# VoltageDivision.net
KiCad netlist of a schematic drawn in Altium Designer
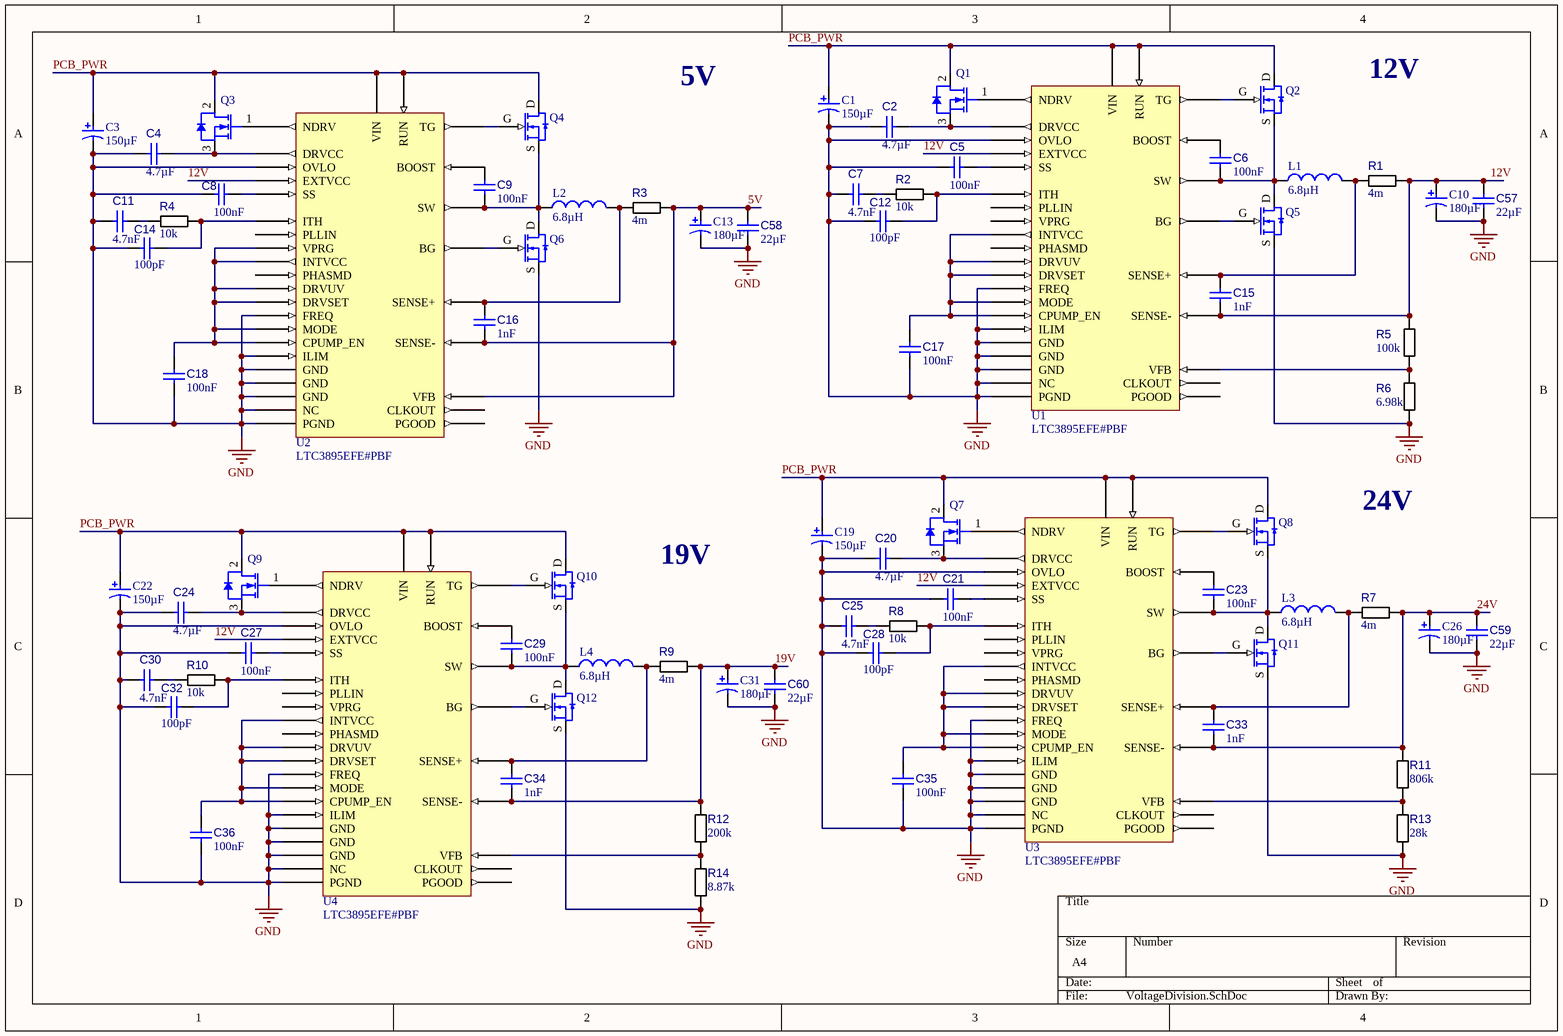
[diagram p0: VoltageDivision.SchDoc]

(export (version "E")
  (design (tool "Eeschema 10.0.6"))
  (components
    (comp (ref "C1")
      (value "150µF")
      (footprint "CAPAE10083X105M")
      (description "Cap Aluminum 150uF 50V 20% Cylindrical 0.34 Ohm 350mA 2000 hr 105°C Emboss T/R")
      (fields (field (name "Comment") "EEE-FN1H151UP"))
      (libsource (lib "Oliver Voorel") (part "CAP-P-2"))
    )
    (comp (ref "C2")
      (value "4.7µF")
      (footprint "FP-GRM31C-0_2-e0_3_0_8-IPC_A")
      (fields (field (name "Comment") "4.7uF 1206"))
      (libsource (lib "Oliver Voorel") (part "CAP-NP-2"))
    )
    (comp (ref "C3")
      (value "150µF")
      (footprint "CAPAE10083X105M")
      (description "Cap Aluminum 150uF 50V 20% Cylindrical 0.34 Ohm 350mA 2000 hr 105°C Emboss T/R")
      (fields (field (name "Comment") "EEE-FN1H151UP"))
      (libsource (lib "Oliver Voorel") (part "CAP-P-2"))
    )
    (comp (ref "C4")
      (value "4.7µF")
      (footprint "FP-GRM31C-0_2-e0_3_0_8-IPC_A")
      (fields (field (name "Comment") "4.7uF 1206"))
      (libsource (lib "Oliver Voorel") (part "CAP-NP-2"))
    )
    (comp (ref "C5")
      (value "100nF")
      (footprint "CAPC1608X10N")
      (fields (field (name "TOLERANCE") "5%") (field (name "Comment") "100nF 0603"))
      (libsource (lib "Oliver Voorel") (part "CAP-NP-2"))
    )
    (comp (ref "C6")
      (value "100nF")
      (footprint "CAPC1608X10N")
      (fields (field (name "TOLERANCE") "5%") (field (name "Comment") "100nF 0603"))
      (libsource (lib "Oliver Voorel") (part "CAP-NP-2"))
    )
    (comp (ref "C7")
      (value "4.7nF")
      (footprint "CAPC1608X10N")
      (fields (field (name "Comment") "CL10B472KB8NNNC"))
      (libsource (lib "Oliver Voorel") (part "CAP-NP-2"))
    )
    (comp (ref "C8")
      (value "100nF")
      (footprint "CAPC1608X10N")
      (fields (field (name "TOLERANCE") "5%") (field (name "Comment") "100nF 0603"))
      (libsource (lib "Oliver Voorel") (part "CAP-NP-2"))
    )
    (comp (ref "C9")
      (value "100nF")
      (footprint "CAPC1608X10N")
      (fields (field (name "TOLERANCE") "5%") (field (name "Comment") "100nF 0603"))
      (libsource (lib "Oliver Voorel") (part "CAP-NP-2"))
    )
    (comp (ref "C10")
      (value "180µF")
      (footprint "CAPAE10083X105M")
      (description "Cap Aluminum 180uF 50V 20% Cylindrical 0.34 Ohm 350mA 2000 hr 105°C Emboss T/R")
      (fields (field (name "TOLERANCE") "20%") (field (name "Comment") "EEEFN1H181UP"))
      (libsource (lib "Oliver Voorel") (part "CAP-P-2"))
    )
    (comp (ref "C11")
      (value "4.7nF")
      (footprint "CAPC1608X10N")
      (fields (field (name "Comment") "CL10B472KB8NNNC"))
      (libsource (lib "Oliver Voorel") (part "CAP-NP-2"))
    )
    (comp (ref "C12")
      (value "100pF")
      (footprint "CAPC1608X10N")
      (description "50V 100pF C0G ±5% 0603 Multilayer Ceramic Capacitors MLCC - SMD/SMT ROHS")
      (fields (field (name "TOLERANCE") "5%") (field (name "Comment") "100pF 0603"))
      (libsource (lib "Oliver Voorel") (part "CAP-NP-2"))
    )
    (comp (ref "C13")
      (value "180µF")
      (footprint "CAPAE10083X105M")
      (description "Cap Aluminum 180uF 50V 20% Cylindrical 0.34 Ohm 350mA 2000 hr 105°C Emboss T/R")
      (fields (field (name "TOLERANCE") "20%") (field (name "Comment") "EEEFN1H181UP"))
      (libsource (lib "Oliver Voorel") (part "CAP-P-2"))
    )
    (comp (ref "C14")
      (value "100pF")
      (footprint "CAPC1608X10N")
      (description "50V 100pF C0G ±5% 0603 Multilayer Ceramic Capacitors MLCC - SMD/SMT ROHS")
      (fields (field (name "TOLERANCE") "5%") (field (name "Comment") "100pF 0603"))
      (libsource (lib "Oliver Voorel") (part "CAP-NP-2"))
    )
    (comp (ref "C15")
      (value "1nF")
      (footprint "CAPC1608X10N")
      (description "50V 1nF X7R ±10% 0603 Multilayer Ceramic Capacitors MLCC - SMD/SMT ROHS")
      (fields (field (name "Comment") "1nF 0603"))
      (libsource (lib "Oliver Voorel") (part "CAP-NP-2"))
    )
    (comp (ref "C16")
      (value "1nF")
      (footprint "CAPC1608X10N")
      (description "50V 1nF X7R ±10% 0603 Multilayer Ceramic Capacitors MLCC - SMD/SMT ROHS")
      (fields (field (name "Comment") "1nF 0603"))
      (libsource (lib "Oliver Voorel") (part "CAP-NP-2"))
    )
    (comp (ref "C17")
      (value "100nF")
      (footprint "CAPC1608X10N")
      (fields (field (name "TOLERANCE") "5%") (field (name "Comment") "100nF 0603"))
      (libsource (lib "Oliver Voorel") (part "CAP-NP-2"))
    )
    (comp (ref "C18")
      (value "100nF")
      (footprint "CAPC1608X10N")
      (fields (field (name "TOLERANCE") "5%") (field (name "Comment") "100nF 0603"))
      (libsource (lib "Oliver Voorel") (part "CAP-NP-2"))
    )
    (comp (ref "C19")
      (value "150µF")
      (footprint "CAPAE10083X105M")
      (description "Cap Aluminum 150uF 50V 20% Cylindrical 0.34 Ohm 350mA 2000 hr 105°C Emboss T/R")
      (fields (field (name "Comment") "EEE-FN1H151UP"))
      (libsource (lib "Oliver Voorel") (part "CAP-P-2"))
    )
    (comp (ref "C20")
      (value "4.7µF")
      (footprint "FP-GRM31C-0_2-e0_3_0_8-IPC_A")
      (fields (field (name "Comment") "4.7uF 1206"))
      (libsource (lib "Oliver Voorel") (part "CAP-NP-2"))
    )
    (comp (ref "C21")
      (value "100nF")
      (footprint "CAPC1608X10N")
      (fields (field (name "TOLERANCE") "5%") (field (name "Comment") "100nF 0603"))
      (libsource (lib "Oliver Voorel") (part "CAP-NP-2"))
    )
    (comp (ref "C22")
      (value "150µF")
      (footprint "CAPAE10083X105M")
      (description "Cap Aluminum 150uF 50V 20% Cylindrical 0.34 Ohm 350mA 2000 hr 105°C Emboss T/R")
      (fields (field (name "Comment") "EEE-FN1H151UP"))
      (libsource (lib "Oliver Voorel") (part "CAP-P-2"))
    )
    (comp (ref "C23")
      (value "100nF")
      (footprint "CAPC1608X10N")
      (fields (field (name "TOLERANCE") "5%") (field (name "Comment") "100nF 0603"))
      (libsource (lib "Oliver Voorel") (part "CAP-NP-2"))
    )
    (comp (ref "C24")
      (value "4.7µF")
      (footprint "FP-GRM31C-0_2-e0_3_0_8-IPC_A")
      (fields (field (name "Comment") "4.7uF 1206"))
      (libsource (lib "Oliver Voorel") (part "CAP-NP-2"))
    )
    (comp (ref "C25")
      (value "4.7nF")
      (footprint "CAPC1608X10N")
      (fields (field (name "Comment") "CL10B472KB8NNNC"))
      (libsource (lib "Oliver Voorel") (part "CAP-NP-2"))
    )
    (comp (ref "C26")
      (value "180µF")
      (footprint "CAPAE10083X105M")
      (description "Cap Aluminum 180uF 50V 20% Cylindrical 0.34 Ohm 350mA 2000 hr 105°C Emboss T/R")
      (fields (field (name "TOLERANCE") "20%") (field (name "Comment") "EEEFN1H181UP"))
      (libsource (lib "Oliver Voorel") (part "CAP-P-2"))
    )
    (comp (ref "C27")
      (value "100nF")
      (footprint "CAPC1608X10N")
      (fields (field (name "TOLERANCE") "5%") (field (name "Comment") "100nF 0603"))
      (libsource (lib "Oliver Voorel") (part "CAP-NP-2"))
    )
    (comp (ref "C28")
      (value "100pF")
      (footprint "CAPC1608X10N")
      (description "50V 100pF C0G ±5% 0603 Multilayer Ceramic Capacitors MLCC - SMD/SMT ROHS")
      (fields (field (name "TOLERANCE") "5%") (field (name "Comment") "100pF 0603"))
      (libsource (lib "Oliver Voorel") (part "CAP-NP-2"))
    )
    (comp (ref "C29")
      (value "100nF")
      (footprint "CAPC1608X10N")
      (fields (field (name "TOLERANCE") "5%") (field (name "Comment") "100nF 0603"))
      (libsource (lib "Oliver Voorel") (part "CAP-NP-2"))
    )
    (comp (ref "C30")
      (value "4.7nF")
      (footprint "CAPC1608X10N")
      (fields (field (name "Comment") "CL10B472KB8NNNC"))
      (libsource (lib "Oliver Voorel") (part "CAP-NP-2"))
    )
    (comp (ref "C31")
      (value "180µF")
      (footprint "CAPAE10083X105M")
      (description "Cap Aluminum 180uF 50V 20% Cylindrical 0.34 Ohm 350mA 2000 hr 105°C Emboss T/R")
      (fields (field (name "TOLERANCE") "20%") (field (name "Comment") "EEEFN1H181UP"))
      (libsource (lib "Oliver Voorel") (part "CAP-P-2"))
    )
    (comp (ref "C32")
      (value "100pF")
      (footprint "CAPC1608X10N")
      (description "50V 100pF C0G ±5% 0603 Multilayer Ceramic Capacitors MLCC - SMD/SMT ROHS")
      (fields (field (name "TOLERANCE") "5%") (field (name "Comment") "100pF 0603"))
      (libsource (lib "Oliver Voorel") (part "CAP-NP-2"))
    )
    (comp (ref "C33")
      (value "1nF")
      (footprint "CAPC1608X10N")
      (description "50V 1nF X7R ±10% 0603 Multilayer Ceramic Capacitors MLCC - SMD/SMT ROHS")
      (fields (field (name "Comment") "1nF 0603"))
      (libsource (lib "Oliver Voorel") (part "CAP-NP-2"))
    )
    (comp (ref "C34")
      (value "1nF")
      (footprint "CAPC1608X10N")
      (description "50V 1nF X7R ±10% 0603 Multilayer Ceramic Capacitors MLCC - SMD/SMT ROHS")
      (fields (field (name "Comment") "1nF 0603"))
      (libsource (lib "Oliver Voorel") (part "CAP-NP-2"))
    )
    (comp (ref "C35")
      (value "100nF")
      (footprint "CAPC1608X10N")
      (fields (field (name "TOLERANCE") "5%") (field (name "Comment") "100nF 0603"))
      (libsource (lib "Oliver Voorel") (part "CAP-NP-2"))
    )
    (comp (ref "C36")
      (value "100nF")
      (footprint "CAPC1608X10N")
      (fields (field (name "TOLERANCE") "5%") (field (name "Comment") "100nF 0603"))
      (libsource (lib "Oliver Voorel") (part "CAP-NP-2"))
    )
    (comp (ref "C57")
      (value "22µF")
      (footprint "CAPC5750X31N")
      (description "50V 22uF X7R ±10% 2220  Multilayer Ceramic Capacitors MLCC - SMD/SMT ROHS")
      (fields (field (name "TOLERANCE") "10%") (field (name "Comment") "FS55X226K500EHG"))
      (libsource (lib "Oliver Voorel") (part "CAP-NP-2"))
    )
    (comp (ref "C58")
      (value "22µF")
      (footprint "CAPC5750X31N")
      (description "50V 22uF X7R ±10% 2220  Multilayer Ceramic Capacitors MLCC - SMD/SMT ROHS")
      (fields (field (name "TOLERANCE") "10%") (field (name "Comment") "FS55X226K500EHG"))
      (libsource (lib "Oliver Voorel") (part "CAP-NP-2"))
    )
    (comp (ref "C59")
      (value "22µF")
      (footprint "CAPC5750X31N")
      (description "50V 22uF X7R ±10% 2220  Multilayer Ceramic Capacitors MLCC - SMD/SMT ROHS")
      (fields (field (name "TOLERANCE") "10%") (field (name "Comment") "FS55X226K500EHG"))
      (libsource (lib "Oliver Voorel") (part "CAP-NP-2"))
    )
    (comp (ref "C60")
      (value "22µF")
      (footprint "CAPC5750X31N")
      (description "50V 22uF X7R ±10% 2220  Multilayer Ceramic Capacitors MLCC - SMD/SMT ROHS")
      (fields (field (name "TOLERANCE") "10%") (field (name "Comment") "FS55X226K500EHG"))
      (libsource (lib "Oliver Voorel") (part "CAP-NP-2"))
    )
    (comp (ref "L1")
      (value "6.8µH")
      (footprint "INDP134126X50N")
      (description "12A 6.8uH ±20% 16A SMD,13.5x12.6mm  Power Inductors ROHS")
      (fields (field (name "TOLERANCE") "20%") (field (name "Comment") "6.8uH"))
      (libsource (lib "Oliver Voorel") (part "IND-2"))
    )
    (comp (ref "L2")
      (value "6.8µH")
      (footprint "INDP134126X50N")
      (description "12A 6.8uH ±20% 16A SMD,13.5x12.6mm  Power Inductors ROHS")
      (fields (field (name "TOLERANCE") "20%") (field (name "Comment") "6.8uH"))
      (libsource (lib "Oliver Voorel") (part "IND-2"))
    )
    (comp (ref "L3")
      (value "6.8µH")
      (footprint "INDP134126X50N")
      (description "12A 6.8uH ±20% 16A SMD,13.5x12.6mm  Power Inductors ROHS")
      (fields (field (name "TOLERANCE") "20%") (field (name "Comment") "6.8uH"))
      (libsource (lib "Oliver Voorel") (part "IND-2"))
    )
    (comp (ref "L4")
      (value "6.8µH")
      (footprint "INDP134126X50N")
      (description "12A 6.8uH ±20% 16A SMD,13.5x12.6mm  Power Inductors ROHS")
      (fields (field (name "TOLERANCE") "20%") (field (name "Comment") "6.8uH"))
      (libsource (lib "Oliver Voorel") (part "IND-2"))
    )
    (comp (ref "Q1")
      (value "IPD320N20N3GATMA1")
      (footprint "INF-PG-TO252-3-11_A_L")
      (libsource (lib "Oliver Voorel") (part "INF-NEMOS-GDS-3"))
    )
    (comp (ref "Q2")
      (value "BSC028N06LS3GATMA1")
      (footprint "INF-PG-TDSON-8-1_V")
      (libsource (lib "Oliver Voorel") (part "N-channel MOSFET"))
    )
    (comp (ref "Q3")
      (value "IPD320N20N3GATMA1")
      (footprint "INF-PG-TO252-3-11_A_L")
      (libsource (lib "Oliver Voorel") (part "INF-NEMOS-GDS-3"))
    )
    (comp (ref "Q4")
      (value "BSC028N06LS3GATMA1")
      (footprint "INF-PG-TDSON-8-1_V")
      (libsource (lib "Oliver Voorel") (part "N-channel MOSFET"))
    )
    (comp (ref "Q5")
      (value "BSC028N06LS3GATMA1")
      (footprint "INF-PG-TDSON-8-1_V")
      (libsource (lib "Oliver Voorel") (part "N-channel MOSFET"))
    )
    (comp (ref "Q6")
      (value "BSC028N06LS3GATMA1")
      (footprint "INF-PG-TDSON-8-1_V")
      (libsource (lib "Oliver Voorel") (part "N-channel MOSFET"))
    )
    (comp (ref "Q7")
      (value "IPD320N20N3GATMA1")
      (footprint "INF-PG-TO252-3-11_A_L")
      (libsource (lib "Oliver Voorel") (part "INF-NEMOS-GDS-3"))
    )
    (comp (ref "Q8")
      (value "BSC028N06LS3GATMA1")
      (footprint "INF-PG-TDSON-8-1_V")
      (libsource (lib "Oliver Voorel") (part "N-channel MOSFET"))
    )
    (comp (ref "Q9")
      (value "IPD320N20N3GATMA1")
      (footprint "INF-PG-TO252-3-11_A_L")
      (libsource (lib "Oliver Voorel") (part "INF-NEMOS-GDS-3"))
    )
    (comp (ref "Q10")
      (value "BSC028N06LS3GATMA1")
      (footprint "INF-PG-TDSON-8-1_V")
      (libsource (lib "Oliver Voorel") (part "N-channel MOSFET"))
    )
    (comp (ref "Q11")
      (value "BSC028N06LS3GATMA1")
      (footprint "INF-PG-TDSON-8-1_V")
      (libsource (lib "Oliver Voorel") (part "N-channel MOSFET"))
    )
    (comp (ref "Q12")
      (value "BSC028N06LS3GATMA1")
      (footprint "INF-PG-TDSON-8-1_V")
      (libsource (lib "Oliver Voorel") (part "N-channel MOSFET"))
    )
    (comp (ref "R1")
      (value "4m")
      (footprint "RESC6432X09N")
      (description "2W 4mΩ ±50ppm/℃ ±1% 2512  Current Sense Resistors/Shunt Resistors ROHS")
      (fields (field (name "TOLERANCE") "1%") (field (name "POWER") "2W"))
      (libsource (lib "Oliver Voorel") (part "RES-2"))
    )
    (comp (ref "R2")
      (value "10k")
      (footprint "RESC1608X06N")
      (fields
        (field (name "POWER") "100mW")
        (field (name "TOLERANCE") "1%")
        (field (name "Comment") "10k 0603")
      )
      (libsource (lib "Oliver Voorel") (part "RES-2"))
    )
    (comp (ref "R3")
      (value "4m")
      (footprint "RESC6432X09N")
      (description "2W 4mΩ ±50ppm/℃ ±1% 2512  Current Sense Resistors/Shunt Resistors ROHS")
      (fields (field (name "TOLERANCE") "1%") (field (name "POWER") "2W"))
      (libsource (lib "Oliver Voorel") (part "RES-2"))
    )
    (comp (ref "R4")
      (value "10k")
      (footprint "RESC1608X06N")
      (fields
        (field (name "POWER") "100mW")
        (field (name "TOLERANCE") "1%")
        (field (name "Comment") "10k 0603")
      )
      (libsource (lib "Oliver Voorel") (part "RES-2"))
    )
    (comp (ref "R5")
      (value "100k")
      (footprint "RESC1608X06N")
      (description "100mW Thick Film Resistors 75V ±100ppm/℃ ±1% 100kΩ 0603 Chip Resistor - Surface Mount ROHS")
      (fields (field (name "POWER") "100mW") (field (name "TOLERANCE") "1%"))
      (libsource (lib "Oliver Voorel") (part "RES-2"))
    )
    (comp (ref "R6")
      (value "6.98k")
      (footprint "RESC1608X06N")
      (description "100mW Thick Film Resistors 75V ±100ppm/℃ ±1% 6.98kΩ 0603 Chip Resistor - Surface Mount ROHS")
      (fields (field (name "POWER") "100mW") (field (name "TOLERANCE") "1%"))
      (libsource (lib "Oliver Voorel") (part "RES-2"))
    )
    (comp (ref "R7")
      (value "4m")
      (footprint "RESC6432X09N")
      (description "2W 4mΩ ±50ppm/℃ ±1% 2512  Current Sense Resistors/Shunt Resistors ROHS")
      (fields (field (name "TOLERANCE") "1%") (field (name "POWER") "2W"))
      (libsource (lib "Oliver Voorel") (part "RES-2"))
    )
    (comp (ref "R8")
      (value "10k")
      (footprint "RESC1608X06N")
      (fields
        (field (name "POWER") "100mW")
        (field (name "TOLERANCE") "1%")
        (field (name "Comment") "10k 0603")
      )
      (libsource (lib "Oliver Voorel") (part "RES-2"))
    )
    (comp (ref "R9")
      (value "4m")
      (footprint "RESC6432X09N")
      (description "2W 4mΩ ±50ppm/℃ ±1% 2512  Current Sense Resistors/Shunt Resistors ROHS")
      (fields (field (name "TOLERANCE") "1%") (field (name "POWER") "2W"))
      (libsource (lib "Oliver Voorel") (part "RES-2"))
    )
    (comp (ref "R10")
      (value "10k")
      (footprint "RESC1608X06N")
      (fields
        (field (name "POWER") "100mW")
        (field (name "TOLERANCE") "1%")
        (field (name "Comment") "10k 0603")
      )
      (libsource (lib "Oliver Voorel") (part "RES-2"))
    )
    (comp (ref "R11")
      (value "806k")
      (footprint "RESC1608X06N")
      (fields
        (field (name "TOLERANCE") "1%")
        (field (name "POWER") "100mW")
        (field (name "Comment") "806k 0603")
      )
      (libsource (lib "Oliver Voorel") (part "RES-2"))
    )
    (comp (ref "R12")
      (value "200k")
      (footprint "RESC1608X06N")
      (fields
        (field (name "TOLERANCE") "1%")
        (field (name "POWER") "100mW")
        (field (name "Comment") "200kR 0603")
      )
      (libsource (lib "Oliver Voorel") (part "RES-2"))
    )
    (comp (ref "R13")
      (value "28k")
      (footprint "RESC1608X06N")
      (fields
        (field (name "TOLERANCE") "1%")
        (field (name "POWER") "100mW")
        (field (name "Comment") "28k 0603")
      )
      (libsource (lib "Oliver Voorel") (part "RES-2"))
    )
    (comp (ref "R14")
      (value "8.87k")
      (footprint "RESC1608X06N")
      (fields
        (field (name "TOLERANCE") "1%")
        (field (name "POWER") "100mW")
        (field (name "Comment") "8.87k 0603")
      )
      (libsource (lib "Oliver Voorel") (part "RES-2"))
    )
    (comp (ref "U1")
      (value "LTC3895EFE#PBF")
      (footprint "TSSOP50P640X120_HS-39N")
      (description "Switching Controller, Current-mode, 900kHz Switching Freq-Max, CMOS, PDSO38")
      (libsource (lib "Oliver Voorel") (part "LTC3895HFE#PBF-Symbol-1"))
    )
    (comp (ref "U2")
      (value "LTC3895EFE#PBF")
      (footprint "TSSOP50P640X120_HS-39N")
      (description "Switching Controller, Current-mode, 900kHz Switching Freq-Max, CMOS, PDSO38")
      (libsource (lib "Oliver Voorel") (part "LTC3895HFE#PBF-Symbol-1"))
    )
    (comp (ref "U3")
      (value "LTC3895EFE#PBF")
      (footprint "TSSOP50P640X120_HS-39N")
      (description "Switching Controller, Current-mode, 900kHz Switching Freq-Max, CMOS, PDSO38")
      (libsource (lib "Oliver Voorel") (part "LTC3895HFE#PBF-Symbol-1"))
    )
    (comp (ref "U4")
      (value "LTC3895EFE#PBF")
      (footprint "TSSOP50P640X120_HS-39N")
      (description "Switching Controller, Current-mode, 900kHz Switching Freq-Max, CMOS, PDSO38")
      (libsource (lib "Oliver Voorel") (part "LTC3895HFE#PBF-Symbol-1"))
    )
  )
  (nets
    (net (code "1") (name "/5V") (class "Default")
      (node (ref "C13") (pin "1") (pinfunction "1_1") (pintype "passive"))
      (node (ref "C16") (pin "1") (pinfunction "1_1") (pintype "passive"))
      (node (ref "C58") (pin "1") (pinfunction "1_1") (pintype "passive"))
      (node (ref "R3") (pin "2") (pinfunction "2_2") (pintype "passive"))
      (node (ref "U2") (pin "4") (pinfunction "SENSE-_4") (pintype "input"))
      (node (ref "U2") (pin "6") (pinfunction "VFB_6") (pintype "input"))
    )
    (net (code "2") (name "/12V") (class "Default")
      (node (ref "C10") (pin "1") (pinfunction "1_1") (pintype "passive"))
      (node (ref "C15") (pin "1") (pinfunction "1_1") (pintype "passive"))
      (node (ref "C57") (pin "1") (pinfunction "1_1") (pintype "passive"))
      (node (ref "R1") (pin "2") (pinfunction "2_2") (pintype "passive"))
      (node (ref "R5") (pin "2") (pinfunction "2_2") (pintype "passive"))
      (node (ref "U1") (pin "32") (pinfunction "EXTVCC_32") (pintype "input"))
      (node (ref "U1") (pin "4") (pinfunction "SENSE-_4") (pintype "input"))
      (node (ref "U2") (pin "32") (pinfunction "EXTVCC_32") (pintype "input"))
      (node (ref "U3") (pin "32") (pinfunction "EXTVCC_32") (pintype "input"))
      (node (ref "U4") (pin "32") (pinfunction "EXTVCC_32") (pintype "input"))
    )
    (net (code "3") (name "/19V") (class "Default")
      (node (ref "C31") (pin "1") (pinfunction "1_1") (pintype "passive"))
      (node (ref "C34") (pin "1") (pinfunction "1_1") (pintype "passive"))
      (node (ref "C60") (pin "1") (pinfunction "1_1") (pintype "passive"))
      (node (ref "R12") (pin "1") (pinfunction "1_1") (pintype "passive"))
      (node (ref "R9") (pin "2") (pinfunction "2_2") (pintype "passive"))
      (node (ref "U4") (pin "4") (pinfunction "SENSE-_4") (pintype "input"))
    )
    (net (code "4") (name "/24V") (class "Default")
      (node (ref "C26") (pin "1") (pinfunction "1_1") (pintype "passive"))
      (node (ref "C33") (pin "1") (pinfunction "1_1") (pintype "passive"))
      (node (ref "C59") (pin "1") (pinfunction "1_1") (pintype "passive"))
      (node (ref "R11") (pin "2") (pinfunction "2_2") (pintype "passive"))
      (node (ref "R7") (pin "2") (pinfunction "2_2") (pintype "passive"))
      (node (ref "U3") (pin "4") (pinfunction "SENSE-_4") (pintype "input"))
    )
    (net (code "5") (name "/PCB_PWR") (class "Default")
      (node (ref "C1") (pin "1") (pinfunction "1_1") (pintype "passive"))
      (node (ref "C19") (pin "1") (pinfunction "1_1") (pintype "passive"))
      (node (ref "C22") (pin "1") (pinfunction "1_1") (pintype "passive"))
      (node (ref "C3") (pin "1") (pinfunction "1_1") (pintype "passive"))
      (node (ref "Q1") (pin "2") (pinfunction "DRAIN_2") (pintype "passive"))
      (node (ref "Q10") (pin "D") (pinfunction "D_D") (pintype "passive"))
      (node (ref "Q2") (pin "D") (pinfunction "D_D") (pintype "passive"))
      (node (ref "Q3") (pin "2") (pinfunction "DRAIN_2") (pintype "passive"))
      (node (ref "Q4") (pin "D") (pinfunction "D_D") (pintype "passive"))
      (node (ref "Q7") (pin "2") (pinfunction "DRAIN_2") (pintype "passive"))
      (node (ref "Q8") (pin "D") (pinfunction "D_D") (pintype "passive"))
      (node (ref "Q9") (pin "2") (pinfunction "DRAIN_2") (pintype "passive"))
      (node (ref "U1") (pin "30") (pinfunction "VIN_30") (pintype "power_in"))
      (node (ref "U1") (pin "34") (pinfunction "RUN_34") (pintype "input"))
      (node (ref "U2") (pin "30") (pinfunction "VIN_30") (pintype "power_in"))
      (node (ref "U2") (pin "34") (pinfunction "RUN_34") (pintype "input"))
      (node (ref "U3") (pin "30") (pinfunction "VIN_30") (pintype "power_in"))
      (node (ref "U3") (pin "34") (pinfunction "RUN_34") (pintype "input"))
      (node (ref "U4") (pin "30") (pinfunction "VIN_30") (pintype "power_in"))
      (node (ref "U4") (pin "34") (pinfunction "RUN_34") (pintype "input"))
    )
    (net (code "6") (name "GND") (class "Default")
      (node (ref "C1") (pin "2") (pinfunction "2_2") (pintype "passive"))
      (node (ref "C10") (pin "2") (pinfunction "2_2") (pintype "passive"))
      (node (ref "C11") (pin "1") (pinfunction "1_1") (pintype "passive"))
      (node (ref "C12") (pin "1") (pinfunction "1_1") (pintype "passive"))
      (node (ref "C13") (pin "2") (pinfunction "2_2") (pintype "passive"))
      (node (ref "C14") (pin "1") (pinfunction "1_1") (pintype "passive"))
      (node (ref "C17") (pin "1") (pinfunction "1_1") (pintype "passive"))
      (node (ref "C18") (pin "1") (pinfunction "1_1") (pintype "passive"))
      (node (ref "C19") (pin "2") (pinfunction "2_2") (pintype "passive"))
      (node (ref "C2") (pin "1") (pinfunction "1_1") (pintype "passive"))
      (node (ref "C20") (pin "1") (pinfunction "1_1") (pintype "passive"))
      (node (ref "C21") (pin "2") (pinfunction "2_2") (pintype "passive"))
      (node (ref "C22") (pin "2") (pinfunction "2_2") (pintype "passive"))
      (node (ref "C24") (pin "1") (pinfunction "1_1") (pintype "passive"))
      (node (ref "C25") (pin "1") (pinfunction "1_1") (pintype "passive"))
      (node (ref "C26") (pin "2") (pinfunction "2_2") (pintype "passive"))
      (node (ref "C27") (pin "2") (pinfunction "2_2") (pintype "passive"))
      (node (ref "C28") (pin "1") (pinfunction "1_1") (pintype "passive"))
      (node (ref "C3") (pin "2") (pinfunction "2_2") (pintype "passive"))
      (node (ref "C30") (pin "1") (pinfunction "1_1") (pintype "passive"))
      (node (ref "C31") (pin "2") (pinfunction "2_2") (pintype "passive"))
      (node (ref "C32") (pin "1") (pinfunction "1_1") (pintype "passive"))
      (node (ref "C35") (pin "1") (pinfunction "1_1") (pintype "passive"))
      (node (ref "C36") (pin "1") (pinfunction "1_1") (pintype "passive"))
      (node (ref "C4") (pin "1") (pinfunction "1_1") (pintype "passive"))
      (node (ref "C5") (pin "2") (pinfunction "2_2") (pintype "passive"))
      (node (ref "C57") (pin "2") (pinfunction "2_2") (pintype "passive"))
      (node (ref "C58") (pin "2") (pinfunction "2_2") (pintype "passive"))
      (node (ref "C59") (pin "2") (pinfunction "2_2") (pintype "passive"))
      (node (ref "C60") (pin "2") (pinfunction "2_2") (pintype "passive"))
      (node (ref "C7") (pin "1") (pinfunction "1_1") (pintype "passive"))
      (node (ref "C8") (pin "2") (pinfunction "2_2") (pintype "passive"))
      (node (ref "Q11") (pin "S") (pinfunction "S_S") (pintype "passive"))
      (node (ref "Q12") (pin "S") (pinfunction "S_S") (pintype "passive"))
      (node (ref "Q5") (pin "S") (pinfunction "S_S") (pintype "passive"))
      (node (ref "Q6") (pin "S") (pinfunction "S_S") (pintype "passive"))
      (node (ref "R13") (pin "1") (pinfunction "1_1") (pintype "passive"))
      (node (ref "R14") (pin "1") (pinfunction "1_1") (pintype "passive"))
      (node (ref "R6") (pin "1") (pinfunction "1_1") (pintype "passive"))
      (node (ref "U1") (pin "1") (pinfunction "OVLO_1") (pintype "input"))
      (node (ref "U1") (pin "12") (pinfunction "GND_12") (pintype "power_in"))
      (node (ref "U1") (pin "15") (pinfunction "GND_15") (pintype "power_in"))
      (node (ref "U1") (pin "16") (pinfunction "NC_16") (pintype "passive"))
      (node (ref "U1") (pin "17") (pinfunction "FREQ_17") (pintype "input"))
      (node (ref "U1") (pin "37") (pinfunction "ILIM_37") (pintype "input"))
      (node (ref "U1") (pin "39") (pinfunction "PGND_39") (pintype "power_in"))
      (node (ref "U1") (pin "9") (pinfunction "GND_9") (pintype "power_in"))
      (node (ref "U2") (pin "1") (pinfunction "OVLO_1") (pintype "input"))
      (node (ref "U2") (pin "12") (pinfunction "GND_12") (pintype "power_in"))
      (node (ref "U2") (pin "15") (pinfunction "GND_15") (pintype "power_in"))
      (node (ref "U2") (pin "16") (pinfunction "NC_16") (pintype "passive"))
      (node (ref "U2") (pin "17") (pinfunction "FREQ_17") (pintype "input"))
      (node (ref "U2") (pin "37") (pinfunction "ILIM_37") (pintype "input"))
      (node (ref "U2") (pin "39") (pinfunction "PGND_39") (pintype "power_in"))
      (node (ref "U2") (pin "9") (pinfunction "GND_9") (pintype "power_in"))
      (node (ref "U3") (pin "1") (pinfunction "OVLO_1") (pintype "input"))
      (node (ref "U3") (pin "12") (pinfunction "GND_12") (pintype "power_in"))
      (node (ref "U3") (pin "15") (pinfunction "GND_15") (pintype "power_in"))
      (node (ref "U3") (pin "16") (pinfunction "NC_16") (pintype "passive"))
      (node (ref "U3") (pin "17") (pinfunction "FREQ_17") (pintype "input"))
      (node (ref "U3") (pin "37") (pinfunction "ILIM_37") (pintype "input"))
      (node (ref "U3") (pin "39") (pinfunction "PGND_39") (pintype "power_in"))
      (node (ref "U3") (pin "9") (pinfunction "GND_9") (pintype "power_in"))
      (node (ref "U4") (pin "1") (pinfunction "OVLO_1") (pintype "input"))
      (node (ref "U4") (pin "12") (pinfunction "GND_12") (pintype "power_in"))
      (node (ref "U4") (pin "15") (pinfunction "GND_15") (pintype "power_in"))
      (node (ref "U4") (pin "16") (pinfunction "NC_16") (pintype "passive"))
      (node (ref "U4") (pin "17") (pinfunction "FREQ_17") (pintype "input"))
      (node (ref "U4") (pin "37") (pinfunction "ILIM_37") (pintype "input"))
      (node (ref "U4") (pin "39") (pinfunction "PGND_39") (pintype "power_in"))
      (node (ref "U4") (pin "9") (pinfunction "GND_9") (pintype "power_in"))
    )
    (net (code "7") (name "Net-(C7-Pad2)") (class "Default")
      (node (ref "C7") (pin "2") (pinfunction "2_2") (pintype "passive"))
      (node (ref "R2") (pin "1") (pinfunction "1_1") (pintype "passive"))
    )
    (net (code "8") (name "Net-(C11-Pad2)") (class "Default")
      (node (ref "C11") (pin "2") (pinfunction "2_2") (pintype "passive"))
      (node (ref "R4") (pin "1") (pinfunction "1_1") (pintype "passive"))
    )
    (net (code "9") (name "Net-(C25-Pad2)") (class "Default")
      (node (ref "C25") (pin "2") (pinfunction "2_2") (pintype "passive"))
      (node (ref "R8") (pin "1") (pinfunction "1_1") (pintype "passive"))
    )
    (net (code "10") (name "Net-(C30-Pad2)") (class "Default")
      (node (ref "C30") (pin "2") (pinfunction "2_2") (pintype "passive"))
      (node (ref "R10") (pin "1") (pinfunction "1_1") (pintype "passive"))
    )
    (net (code "11") (name "Net-(Q1-GATE)") (class "Default")
      (node (ref "Q1") (pin "1") (pinfunction "GATE_1") (pintype "passive"))
      (node (ref "U1") (pin "28") (pinfunction "NDRV_28") (pintype "output"))
    )
    (net (code "12") (name "Net-(Q1-SOURCE)") (class "Default")
      (node (ref "C2") (pin "2") (pinfunction "2_2") (pintype "passive"))
      (node (ref "Q1") (pin "3") (pinfunction "SOURCE_3") (pintype "passive"))
      (node (ref "U1") (pin "26") (pinfunction "DRVCC_26") (pintype "output"))
    )
    (net (code "13") (name "Net-(Q3-GATE)") (class "Default")
      (node (ref "Q3") (pin "1") (pinfunction "GATE_1") (pintype "passive"))
      (node (ref "U2") (pin "28") (pinfunction "NDRV_28") (pintype "output"))
    )
    (net (code "14") (name "Net-(Q3-SOURCE)") (class "Default")
      (node (ref "C4") (pin "2") (pinfunction "2_2") (pintype "passive"))
      (node (ref "Q3") (pin "3") (pinfunction "SOURCE_3") (pintype "passive"))
      (node (ref "U2") (pin "26") (pinfunction "DRVCC_26") (pintype "output"))
    )
    (net (code "15") (name "Net-(Q7-GATE)") (class "Default")
      (node (ref "Q7") (pin "1") (pinfunction "GATE_1") (pintype "passive"))
      (node (ref "U3") (pin "28") (pinfunction "NDRV_28") (pintype "output"))
    )
    (net (code "16") (name "Net-(Q7-SOURCE)") (class "Default")
      (node (ref "C20") (pin "2") (pinfunction "2_2") (pintype "passive"))
      (node (ref "Q7") (pin "3") (pinfunction "SOURCE_3") (pintype "passive"))
      (node (ref "U3") (pin "26") (pinfunction "DRVCC_26") (pintype "output"))
    )
    (net (code "17") (name "Net-(Q9-GATE)") (class "Default")
      (node (ref "Q9") (pin "1") (pinfunction "GATE_1") (pintype "passive"))
      (node (ref "U4") (pin "28") (pinfunction "NDRV_28") (pintype "output"))
    )
    (net (code "18") (name "Net-(Q9-SOURCE)") (class "Default")
      (node (ref "C24") (pin "2") (pinfunction "2_2") (pintype "passive"))
      (node (ref "Q9") (pin "3") (pinfunction "SOURCE_3") (pintype "passive"))
      (node (ref "U4") (pin "26") (pinfunction "DRVCC_26") (pintype "output"))
    )
    (net (code "19") (name "Net-(U1-BG)") (class "Default")
      (node (ref "Q5") (pin "G") (pinfunction "G_G") (pintype "input"))
      (node (ref "U1") (pin "24") (pinfunction "BG_24") (pintype "output"))
    )
    (net (code "20") (name "Net-(U1-BOOST)") (class "Default")
      (node (ref "C6") (pin "2") (pinfunction "2_2") (pintype "passive"))
      (node (ref "U1") (pin "22") (pinfunction "BOOST_22") (pintype "input"))
    )
    (net (code "21") (name "Net-(U1-CPUMP_EN)") (class "Default")
      (node (ref "C17") (pin "2") (pinfunction "2_2") (pintype "passive"))
      (node (ref "U1") (pin "10") (pinfunction "CPUMP_EN_10") (pintype "input"))
      (node (ref "U1") (pin "18") (pinfunction "DRVSET_18") (pintype "input"))
      (node (ref "U1") (pin "19") (pinfunction "DRVUV_19") (pintype "input"))
      (node (ref "U1") (pin "38") (pinfunction "INTVCC_38") (pintype "output"))
      (node (ref "U1") (pin "8") (pinfunction "MODE_8") (pintype "input"))
    )
    (net (code "22") (name "Net-(U1-ITH)") (class "Default")
      (node (ref "C12") (pin "2") (pinfunction "2_2") (pintype "passive"))
      (node (ref "R2") (pin "2") (pinfunction "2_2") (pintype "passive"))
      (node (ref "U1") (pin "7") (pinfunction "ITH_7") (pintype "input"))
    )
    (net (code "23") (name "Net-(U1-SENSE+)") (class "Default")
      (node (ref "C15") (pin "2") (pinfunction "2_2") (pintype "passive"))
      (node (ref "L1") (pin "2") (pinfunction "2_2") (pintype "passive"))
      (node (ref "R1") (pin "1") (pinfunction "1_1") (pintype "passive"))
      (node (ref "U1") (pin "3") (pinfunction "SENSE+_3") (pintype "input"))
    )
    (net (code "24") (name "Net-(U1-SS)") (class "Default")
      (node (ref "C5") (pin "1") (pinfunction "1_1") (pintype "passive"))
      (node (ref "U1") (pin "5") (pinfunction "SS_5") (pintype "input"))
    )
    (net (code "25") (name "Net-(U1-SW)") (class "Default")
      (node (ref "C6") (pin "1") (pinfunction "1_1") (pintype "passive"))
      (node (ref "L1") (pin "1") (pinfunction "1_1") (pintype "passive"))
      (node (ref "Q2") (pin "S") (pinfunction "S_S") (pintype "passive"))
      (node (ref "Q5") (pin "D") (pinfunction "D_D") (pintype "passive"))
      (node (ref "U1") (pin "21") (pinfunction "SW_21") (pintype "output"))
    )
    (net (code "26") (name "Net-(U1-TG)") (class "Default")
      (node (ref "Q2") (pin "G") (pinfunction "G_G") (pintype "input"))
      (node (ref "U1") (pin "20") (pinfunction "TG_20") (pintype "output"))
    )
    (net (code "27") (name "Net-(U1-VFB)") (class "Default")
      (node (ref "R5") (pin "1") (pinfunction "1_1") (pintype "passive"))
      (node (ref "R6") (pin "2") (pinfunction "2_2") (pintype "passive"))
      (node (ref "U1") (pin "6") (pinfunction "VFB_6") (pintype "input"))
    )
    (net (code "28") (name "Net-(U2-BG)") (class "Default")
      (node (ref "Q6") (pin "G") (pinfunction "G_G") (pintype "input"))
      (node (ref "U2") (pin "24") (pinfunction "BG_24") (pintype "output"))
    )
    (net (code "29") (name "Net-(U2-BOOST)") (class "Default")
      (node (ref "C9") (pin "2") (pinfunction "2_2") (pintype "passive"))
      (node (ref "U2") (pin "22") (pinfunction "BOOST_22") (pintype "input"))
    )
    (net (code "30") (name "Net-(U2-CPUMP_EN)") (class "Default")
      (node (ref "C18") (pin "2") (pinfunction "2_2") (pintype "passive"))
      (node (ref "U2") (pin "10") (pinfunction "CPUMP_EN_10") (pintype "input"))
      (node (ref "U2") (pin "18") (pinfunction "DRVSET_18") (pintype "input"))
      (node (ref "U2") (pin "19") (pinfunction "DRVUV_19") (pintype "input"))
      (node (ref "U2") (pin "2") (pinfunction "VPRG_2") (pintype "input"))
      (node (ref "U2") (pin "38") (pinfunction "INTVCC_38") (pintype "output"))
      (node (ref "U2") (pin "8") (pinfunction "MODE_8") (pintype "input"))
    )
    (net (code "31") (name "Net-(U2-ITH)") (class "Default")
      (node (ref "C14") (pin "2") (pinfunction "2_2") (pintype "passive"))
      (node (ref "R4") (pin "2") (pinfunction "2_2") (pintype "passive"))
      (node (ref "U2") (pin "7") (pinfunction "ITH_7") (pintype "input"))
    )
    (net (code "32") (name "Net-(U2-SENSE+)") (class "Default")
      (node (ref "C16") (pin "2") (pinfunction "2_2") (pintype "passive"))
      (node (ref "L2") (pin "2") (pinfunction "2_2") (pintype "passive"))
      (node (ref "R3") (pin "1") (pinfunction "1_1") (pintype "passive"))
      (node (ref "U2") (pin "3") (pinfunction "SENSE+_3") (pintype "input"))
    )
    (net (code "33") (name "Net-(U2-SS)") (class "Default")
      (node (ref "C8") (pin "1") (pinfunction "1_1") (pintype "passive"))
      (node (ref "U2") (pin "5") (pinfunction "SS_5") (pintype "input"))
    )
    (net (code "34") (name "Net-(U2-SW)") (class "Default")
      (node (ref "C9") (pin "1") (pinfunction "1_1") (pintype "passive"))
      (node (ref "L2") (pin "1") (pinfunction "1_1") (pintype "passive"))
      (node (ref "Q4") (pin "S") (pinfunction "S_S") (pintype "passive"))
      (node (ref "Q6") (pin "D") (pinfunction "D_D") (pintype "passive"))
      (node (ref "U2") (pin "21") (pinfunction "SW_21") (pintype "output"))
    )
    (net (code "35") (name "Net-(U2-TG)") (class "Default")
      (node (ref "Q4") (pin "G") (pinfunction "G_G") (pintype "input"))
      (node (ref "U2") (pin "20") (pinfunction "TG_20") (pintype "output"))
    )
    (net (code "36") (name "Net-(U3-BG)") (class "Default")
      (node (ref "Q11") (pin "G") (pinfunction "G_G") (pintype "input"))
      (node (ref "U3") (pin "24") (pinfunction "BG_24") (pintype "output"))
    )
    (net (code "37") (name "Net-(U3-BOOST)") (class "Default")
      (node (ref "C23") (pin "2") (pinfunction "2_2") (pintype "passive"))
      (node (ref "U3") (pin "22") (pinfunction "BOOST_22") (pintype "input"))
    )
    (net (code "38") (name "Net-(U3-CPUMP_EN)") (class "Default")
      (node (ref "C35") (pin "2") (pinfunction "2_2") (pintype "passive"))
      (node (ref "U3") (pin "10") (pinfunction "CPUMP_EN_10") (pintype "input"))
      (node (ref "U3") (pin "18") (pinfunction "DRVSET_18") (pintype "input"))
      (node (ref "U3") (pin "19") (pinfunction "DRVUV_19") (pintype "input"))
      (node (ref "U3") (pin "38") (pinfunction "INTVCC_38") (pintype "output"))
      (node (ref "U3") (pin "8") (pinfunction "MODE_8") (pintype "input"))
    )
    (net (code "39") (name "Net-(U3-ITH)") (class "Default")
      (node (ref "C28") (pin "2") (pinfunction "2_2") (pintype "passive"))
      (node (ref "R8") (pin "2") (pinfunction "2_2") (pintype "passive"))
      (node (ref "U3") (pin "7") (pinfunction "ITH_7") (pintype "input"))
    )
    (net (code "40") (name "Net-(U3-SENSE+)") (class "Default")
      (node (ref "C33") (pin "2") (pinfunction "2_2") (pintype "passive"))
      (node (ref "L3") (pin "2") (pinfunction "2_2") (pintype "passive"))
      (node (ref "R7") (pin "1") (pinfunction "1_1") (pintype "passive"))
      (node (ref "U3") (pin "3") (pinfunction "SENSE+_3") (pintype "input"))
    )
    (net (code "41") (name "Net-(U3-SS)") (class "Default")
      (node (ref "C21") (pin "1") (pinfunction "1_1") (pintype "passive"))
      (node (ref "U3") (pin "5") (pinfunction "SS_5") (pintype "input"))
    )
    (net (code "42") (name "Net-(U3-SW)") (class "Default")
      (node (ref "C23") (pin "1") (pinfunction "1_1") (pintype "passive"))
      (node (ref "L3") (pin "1") (pinfunction "1_1") (pintype "passive"))
      (node (ref "Q11") (pin "D") (pinfunction "D_D") (pintype "passive"))
      (node (ref "Q8") (pin "S") (pinfunction "S_S") (pintype "passive"))
      (node (ref "U3") (pin "21") (pinfunction "SW_21") (pintype "output"))
    )
    (net (code "43") (name "Net-(U3-TG)") (class "Default")
      (node (ref "Q8") (pin "G") (pinfunction "G_G") (pintype "input"))
      (node (ref "U3") (pin "20") (pinfunction "TG_20") (pintype "output"))
    )
    (net (code "44") (name "Net-(U3-VFB)") (class "Default")
      (node (ref "R11") (pin "1") (pinfunction "1_1") (pintype "passive"))
      (node (ref "R13") (pin "2") (pinfunction "2_2") (pintype "passive"))
      (node (ref "U3") (pin "6") (pinfunction "VFB_6") (pintype "input"))
    )
    (net (code "45") (name "Net-(U4-BG)") (class "Default")
      (node (ref "Q12") (pin "G") (pinfunction "G_G") (pintype "input"))
      (node (ref "U4") (pin "24") (pinfunction "BG_24") (pintype "output"))
    )
    (net (code "46") (name "Net-(U4-BOOST)") (class "Default")
      (node (ref "C29") (pin "2") (pinfunction "2_2") (pintype "passive"))
      (node (ref "U4") (pin "22") (pinfunction "BOOST_22") (pintype "input"))
    )
    (net (code "47") (name "Net-(U4-CPUMP_EN)") (class "Default")
      (node (ref "C36") (pin "2") (pinfunction "2_2") (pintype "passive"))
      (node (ref "U4") (pin "10") (pinfunction "CPUMP_EN_10") (pintype "input"))
      (node (ref "U4") (pin "18") (pinfunction "DRVSET_18") (pintype "input"))
      (node (ref "U4") (pin "19") (pinfunction "DRVUV_19") (pintype "input"))
      (node (ref "U4") (pin "38") (pinfunction "INTVCC_38") (pintype "output"))
      (node (ref "U4") (pin "8") (pinfunction "MODE_8") (pintype "input"))
    )
    (net (code "48") (name "Net-(U4-ITH)") (class "Default")
      (node (ref "C32") (pin "2") (pinfunction "2_2") (pintype "passive"))
      (node (ref "R10") (pin "2") (pinfunction "2_2") (pintype "passive"))
      (node (ref "U4") (pin "7") (pinfunction "ITH_7") (pintype "input"))
    )
    (net (code "49") (name "Net-(U4-SENSE+)") (class "Default")
      (node (ref "C34") (pin "2") (pinfunction "2_2") (pintype "passive"))
      (node (ref "L4") (pin "2") (pinfunction "2_2") (pintype "passive"))
      (node (ref "R9") (pin "1") (pinfunction "1_1") (pintype "passive"))
      (node (ref "U4") (pin "3") (pinfunction "SENSE+_3") (pintype "input"))
    )
    (net (code "50") (name "Net-(U4-SS)") (class "Default")
      (node (ref "C27") (pin "1") (pinfunction "1_1") (pintype "passive"))
      (node (ref "U4") (pin "5") (pinfunction "SS_5") (pintype "input"))
    )
    (net (code "51") (name "Net-(U4-SW)") (class "Default")
      (node (ref "C29") (pin "1") (pinfunction "1_1") (pintype "passive"))
      (node (ref "L4") (pin "1") (pinfunction "1_1") (pintype "passive"))
      (node (ref "Q10") (pin "S") (pinfunction "S_S") (pintype "passive"))
      (node (ref "Q12") (pin "D") (pinfunction "D_D") (pintype "passive"))
      (node (ref "U4") (pin "21") (pinfunction "SW_21") (pintype "output"))
    )
    (net (code "52") (name "Net-(U4-TG)") (class "Default")
      (node (ref "Q10") (pin "G") (pinfunction "G_G") (pintype "input"))
      (node (ref "U4") (pin "20") (pinfunction "TG_20") (pintype "output"))
    )
    (net (code "53") (name "Net-(U4-VFB)") (class "Default")
      (node (ref "R12") (pin "2") (pinfunction "2_2") (pintype "passive"))
      (node (ref "R14") (pin "2") (pinfunction "2_2") (pintype "passive"))
      (node (ref "U4") (pin "6") (pinfunction "VFB_6") (pintype "input"))
    )
    (net (code "54") (name "unconnected-(U1-CLKOUT-Pad11)") (class "Default")
      (node (ref "U1") (pin "11") (pinfunction "CLKOUT_11") (pintype "output"))
    )
    (net (code "55") (name "unconnected-(U1-PGOOD-Pad14)") (class "Default")
      (node (ref "U1") (pin "14") (pinfunction "PGOOD_14") (pintype "output"))
    )
    (net (code "56") (name "unconnected-(U1-PHASMD-Pad36)") (class "Default")
      (node (ref "U1") (pin "36") (pinfunction "PHASMD_36") (pintype "input"))
    )
    (net (code "57") (name "unconnected-(U1-PLLIN-Pad13)") (class "Default")
      (node (ref "U1") (pin "13") (pinfunction "PLLIN_13") (pintype "input"))
    )
    (net (code "58") (name "unconnected-(U1-VPRG-Pad2)") (class "Default")
      (node (ref "U1") (pin "2") (pinfunction "VPRG_2") (pintype "input"))
    )
    (net (code "59") (name "unconnected-(U2-CLKOUT-Pad11)") (class "Default")
      (node (ref "U2") (pin "11") (pinfunction "CLKOUT_11") (pintype "output"))
    )
    (net (code "60") (name "unconnected-(U2-PGOOD-Pad14)") (class "Default")
      (node (ref "U2") (pin "14") (pinfunction "PGOOD_14") (pintype "output"))
    )
    (net (code "61") (name "unconnected-(U2-PHASMD-Pad36)") (class "Default")
      (node (ref "U2") (pin "36") (pinfunction "PHASMD_36") (pintype "input"))
    )
    (net (code "62") (name "unconnected-(U2-PLLIN-Pad13)") (class "Default")
      (node (ref "U2") (pin "13") (pinfunction "PLLIN_13") (pintype "input"))
    )
    (net (code "63") (name "unconnected-(U3-CLKOUT-Pad11)") (class "Default")
      (node (ref "U3") (pin "11") (pinfunction "CLKOUT_11") (pintype "output"))
    )
    (net (code "64") (name "unconnected-(U3-PGOOD-Pad14)") (class "Default")
      (node (ref "U3") (pin "14") (pinfunction "PGOOD_14") (pintype "output"))
    )
    (net (code "65") (name "unconnected-(U3-PHASMD-Pad36)") (class "Default")
      (node (ref "U3") (pin "36") (pinfunction "PHASMD_36") (pintype "input"))
    )
    (net (code "66") (name "unconnected-(U3-PLLIN-Pad13)") (class "Default")
      (node (ref "U3") (pin "13") (pinfunction "PLLIN_13") (pintype "input"))
    )
    (net (code "67") (name "unconnected-(U3-VPRG-Pad2)") (class "Default")
      (node (ref "U3") (pin "2") (pinfunction "VPRG_2") (pintype "input"))
    )
    (net (code "68") (name "unconnected-(U4-CLKOUT-Pad11)") (class "Default")
      (node (ref "U4") (pin "11") (pinfunction "CLKOUT_11") (pintype "output"))
    )
    (net (code "69") (name "unconnected-(U4-PGOOD-Pad14)") (class "Default")
      (node (ref "U4") (pin "14") (pinfunction "PGOOD_14") (pintype "output"))
    )
    (net (code "70") (name "unconnected-(U4-PHASMD-Pad36)") (class "Default")
      (node (ref "U4") (pin "36") (pinfunction "PHASMD_36") (pintype "input"))
    )
    (net (code "71") (name "unconnected-(U4-PLLIN-Pad13)") (class "Default")
      (node (ref "U4") (pin "13") (pinfunction "PLLIN_13") (pintype "input"))
    )
    (net (code "72") (name "unconnected-(U4-VPRG-Pad2)") (class "Default")
      (node (ref "U4") (pin "2") (pinfunction "VPRG_2") (pintype "input"))
    )
  )
)
